# pulser_5.net
KiCad netlist of a schematic drawn in EAGLE
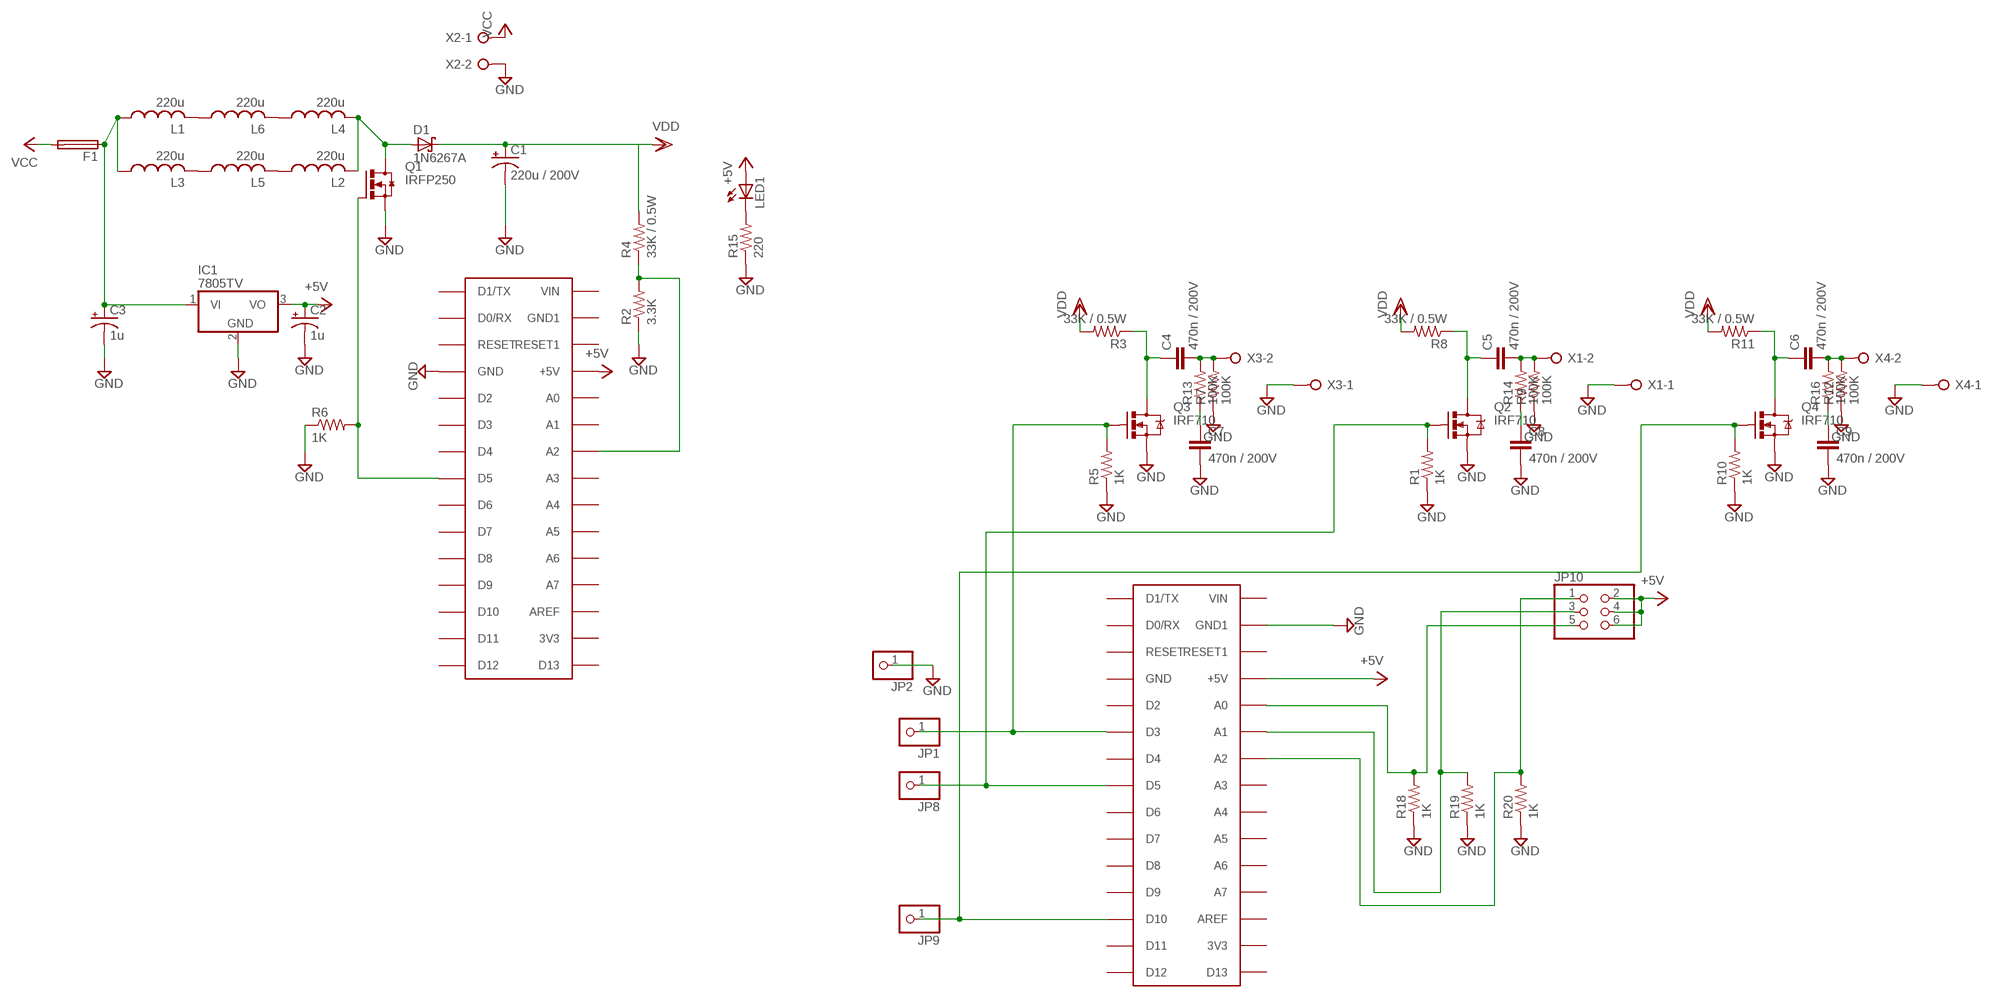
[diagram p0: schematic, sheet 1]

(export (version "E")
  (design (tool "Eeschema 10.0.6"))
  (components
    (comp (ref "C1")
      (value "220u / 200V")
      (footprint "eagle-import:E7,5-18")
      (libsource (lib "eagle-import") (part "CPOL-USE7.5-18"))
    )
    (comp (ref "C2")
      (value "1u")
      (footprint "eagle-import:E2,5-6")
      (libsource (lib "eagle-import") (part "CPOL-USE2.5-6"))
    )
    (comp (ref "C3")
      (value "1u")
      (footprint "eagle-import:E2,5-6")
      (libsource (lib "eagle-import") (part "CPOL-USE2.5-6"))
    )
    (comp (ref "C4")
      (value "470n / 200V")
      (footprint "eagle-import:C150-064X183")
      (libsource (lib "eagle-import") (part "C-EU150-064X183"))
    )
    (comp (ref "C5")
      (value "470n / 200V")
      (footprint "eagle-import:C150-064X183")
      (libsource (lib "eagle-import") (part "C-EU150-064X183"))
    )
    (comp (ref "C6")
      (value "470n / 200V")
      (footprint "eagle-import:C150-064X183")
      (libsource (lib "eagle-import") (part "C-EU150-064X183"))
    )
    (comp (ref "C7")
      (value "470n / 200V")
      (footprint "eagle-import:C150-064X183")
      (libsource (lib "eagle-import") (part "C-EU150-064X183"))
    )
    (comp (ref "C8")
      (value "470n / 200V")
      (footprint "eagle-import:C150-064X183")
      (libsource (lib "eagle-import") (part "C-EU150-064X183"))
    )
    (comp (ref "C9")
      (value "470n / 200V")
      (footprint "eagle-import:C150-064X183")
      (libsource (lib "eagle-import") (part "C-EU150-064X183"))
    )
    (comp (ref "D1")
      (value "1N6267A")
      (footprint "eagle-import:C4111-15")
      (libsource (lib "eagle-import") (part "1N6267A"))
    )
    (comp (ref "F1")
      (value "TE5")
      (footprint "eagle-import:TE5")
      (libsource (lib "eagle-import") (part "TE5"))
    )
    (comp (ref "IC1")
      (value "7805TV")
      (footprint "eagle-import:TO220V")
      (libsource (lib "eagle-import") (part "78TV05"))
    )
    (comp (ref "JP1")
      (value "PINHD-1X1")
      (footprint "eagle-import:1X01")
      (libsource (lib "eagle-import") (part "PINHD-1X1"))
    )
    (comp (ref "JP2")
      (value "PINHD-1X1")
      (footprint "eagle-import:1X01")
      (libsource (lib "eagle-import") (part "PINHD-1X1"))
    )
    (comp (ref "JP8")
      (value "PINHD-1X1")
      (footprint "eagle-import:1X01")
      (libsource (lib "eagle-import") (part "PINHD-1X1"))
    )
    (comp (ref "JP9")
      (value "PINHD-1X1")
      (footprint "eagle-import:1X01")
      (libsource (lib "eagle-import") (part "PINHD-1X1"))
    )
    (comp (ref "JP10")
      (value "PINHD-2X3")
      (footprint "eagle-import:2X03")
      (libsource (lib "eagle-import") (part "PINHD-2X3"))
    )
    (comp (ref "L1")
      (value "220u")
      (footprint "eagle-import:LAP02KR")
      (libsource (lib "eagle-import") (part "L-USLAP02KR"))
    )
    (comp (ref "L2")
      (value "220u")
      (footprint "eagle-import:LAP02KR")
      (libsource (lib "eagle-import") (part "L-USLAP02KR"))
    )
    (comp (ref "L3")
      (value "220u")
      (footprint "eagle-import:LAP02KR")
      (libsource (lib "eagle-import") (part "L-USLAP02KR"))
    )
    (comp (ref "L4")
      (value "220u")
      (footprint "eagle-import:LAP02KR")
      (libsource (lib "eagle-import") (part "L-USLAP02KR"))
    )
    (comp (ref "L5")
      (value "220u")
      (footprint "eagle-import:LAP02KR")
      (libsource (lib "eagle-import") (part "L-USLAP02KR"))
    )
    (comp (ref "L6")
      (value "220u")
      (footprint "eagle-import:LAP02KR")
      (libsource (lib "eagle-import") (part "L-USLAP02KR"))
    )
    (comp (ref "LED1")
      (value "LED5MM")
      (footprint "eagle-import:LED5MM")
      (libsource (lib "eagle-import") (part "LED5MM"))
    )
    (comp (ref "Q1")
      (value "IRFP250")
      (footprint "eagle-import:TO-247AD-V")
      (libsource (lib "eagle-import") (part "IRFP250"))
    )
    (comp (ref "Q2")
      (value "IRF710")
      (footprint "eagle-import:TO220V")
      (libsource (lib "eagle-import") (part "MOSFET-NCHANNELFQP30N06L"))
    )
    (comp (ref "Q3")
      (value "IRF710")
      (footprint "eagle-import:TO220V")
      (libsource (lib "eagle-import") (part "MOSFET-NCHANNELFQP30N06L"))
    )
    (comp (ref "Q4")
      (value "IRF710")
      (footprint "eagle-import:TO220V")
      (libsource (lib "eagle-import") (part "MOSFET-NCHANNELFQP30N06L"))
    )
    (comp (ref "R1")
      (value "1K")
      (footprint "eagle-import:0207_10")
      (libsource (lib "eagle-import") (part "R-US_0207/10"))
    )
    (comp (ref "R2")
      (value "3.3K")
      (footprint "eagle-import:0207_10")
      (libsource (lib "eagle-import") (part "R-US_0207/10"))
    )
    (comp (ref "R3")
      (value "33K / 0.5W")
      (footprint "eagle-import:0309_12")
      (libsource (lib "eagle-import") (part "R-US_0309/12"))
    )
    (comp (ref "R4")
      (value "33K / 0.5W")
      (footprint "eagle-import:0309_12")
      (libsource (lib "eagle-import") (part "R-US_0309/12"))
    )
    (comp (ref "R5")
      (value "1K")
      (footprint "eagle-import:0207_10")
      (libsource (lib "eagle-import") (part "R-US_0207/10"))
    )
    (comp (ref "R6")
      (value "1K")
      (footprint "eagle-import:0207_10")
      (libsource (lib "eagle-import") (part "R-US_0207/10"))
    )
    (comp (ref "R7")
      (value "100K")
      (footprint "eagle-import:0207_10")
      (libsource (lib "eagle-import") (part "R-US_0207/10"))
    )
    (comp (ref "R8")
      (value "33K / 0.5W")
      (footprint "eagle-import:0309_12")
      (libsource (lib "eagle-import") (part "R-US_0309/12"))
    )
    (comp (ref "R9")
      (value "100K")
      (footprint "eagle-import:0207_10")
      (libsource (lib "eagle-import") (part "R-US_0207/10"))
    )
    (comp (ref "R10")
      (value "1K")
      (footprint "eagle-import:0207_10")
      (libsource (lib "eagle-import") (part "R-US_0207/10"))
    )
    (comp (ref "R11")
      (value "33K / 0.5W")
      (footprint "eagle-import:0309_12")
      (libsource (lib "eagle-import") (part "R-US_0309/12"))
    )
    (comp (ref "R12")
      (value "100K")
      (footprint "eagle-import:0207_10")
      (libsource (lib "eagle-import") (part "R-US_0207/10"))
    )
    (comp (ref "R13")
      (value "100K")
      (footprint "eagle-import:0207_10")
      (libsource (lib "eagle-import") (part "R-US_0207/10"))
    )
    (comp (ref "R14")
      (value "100K")
      (footprint "eagle-import:0207_10")
      (libsource (lib "eagle-import") (part "R-US_0207/10"))
    )
    (comp (ref "R15")
      (value "220")
      (footprint "eagle-import:0207_10")
      (libsource (lib "eagle-import") (part "R-US_0207/10"))
    )
    (comp (ref "R16")
      (value "100K")
      (footprint "eagle-import:0207_10")
      (libsource (lib "eagle-import") (part "R-US_0207/10"))
    )
    (comp (ref "R18")
      (value "1K")
      (footprint "eagle-import:0207_10")
      (libsource (lib "eagle-import") (part "R-US_0207/10"))
    )
    (comp (ref "R19")
      (value "1K")
      (footprint "eagle-import:0207_10")
      (libsource (lib "eagle-import") (part "R-US_0207/10"))
    )
    (comp (ref "R20")
      (value "1K")
      (footprint "eagle-import:0207_10")
      (libsource (lib "eagle-import") (part "R-US_0207/10"))
    )
    (comp (ref "U$1")
      (value "ARDUINONANO")
      (footprint "eagle-import:PDIP-32")
      (libsource (lib "eagle-import") (part "ARDUINONANO"))
    )
    (comp (ref "U$2")
      (value "ARDUINONANO")
      (footprint "eagle-import:PDIP-32")
      (libsource (lib "eagle-import") (part "ARDUINONANO"))
    )
    (comp (ref "X1")
      (value "W237-02P")
      (footprint "eagle-import:W237-132")
      (libsource (lib "eagle-import") (part "W237-02P"))
    )
    (comp (ref "X2")
      (value "W237-02P")
      (footprint "eagle-import:W237-132")
      (libsource (lib "eagle-import") (part "W237-02P"))
    )
    (comp (ref "X3")
      (value "W237-02P")
      (footprint "eagle-import:W237-132")
      (libsource (lib "eagle-import") (part "W237-02P"))
    )
    (comp (ref "X4")
      (value "W237-02P")
      (footprint "eagle-import:W237-132")
      (libsource (lib "eagle-import") (part "W237-02P"))
    )
  )
  (nets
    (net (code "1") (name "+5V") (class "Default")
      (node (ref "C2") (pin "+") (pinfunction "+_+") (pintype "passive"))
      (node (ref "IC1") (pin "3") (pinfunction "VO_3") (pintype "passive"))
      (node (ref "JP10") (pin "2") (pinfunction "2_2") (pintype "passive"))
      (node (ref "JP10") (pin "4") (pinfunction "4_4") (pintype "passive"))
      (node (ref "JP10") (pin "6") (pinfunction "6_6") (pintype "passive"))
      (node (ref "LED1") (pin "A") (pinfunction "A_A") (pintype "passive"))
      (node (ref "U$1") (pin "+5V") (pinfunction "+5V_+5V") (pintype "bidirectional"))
      (node (ref "U$2") (pin "+5V") (pinfunction "+5V_+5V") (pintype "bidirectional"))
    )
    (net (code "2") (name "GND") (class "Default")
      (node (ref "C1") (pin "-") (pinfunction "-_-") (pintype "passive"))
      (node (ref "C2") (pin "-") (pinfunction "-_-") (pintype "passive"))
      (node (ref "C3") (pin "-") (pinfunction "-_-") (pintype "passive"))
      (node (ref "C7") (pin "2") (pinfunction "2_2") (pintype "passive"))
      (node (ref "C8") (pin "2") (pinfunction "2_2") (pintype "passive"))
      (node (ref "C9") (pin "2") (pinfunction "2_2") (pintype "passive"))
      (node (ref "IC1") (pin "2") (pinfunction "GND_2") (pintype "passive"))
      (node (ref "JP2") (pin "1") (pinfunction "1_1") (pintype "passive"))
      (node (ref "Q1") (pin "S") (pinfunction "S_S") (pintype "passive"))
      (node (ref "Q2") (pin "3") (pinfunction "S_3") (pintype "passive"))
      (node (ref "Q3") (pin "3") (pinfunction "S_3") (pintype "passive"))
      (node (ref "Q4") (pin "3") (pinfunction "S_3") (pintype "passive"))
      (node (ref "R1") (pin "1") (pinfunction "1_1") (pintype "passive"))
      (node (ref "R10") (pin "1") (pinfunction "1_1") (pintype "passive"))
      (node (ref "R12") (pin "1") (pinfunction "1_1") (pintype "passive"))
      (node (ref "R15") (pin "1") (pinfunction "1_1") (pintype "passive"))
      (node (ref "R18") (pin "1") (pinfunction "1_1") (pintype "passive"))
      (node (ref "R19") (pin "1") (pinfunction "1_1") (pintype "passive"))
      (node (ref "R2") (pin "1") (pinfunction "1_1") (pintype "passive"))
      (node (ref "R20") (pin "1") (pinfunction "1_1") (pintype "passive"))
      (node (ref "R5") (pin "1") (pinfunction "1_1") (pintype "passive"))
      (node (ref "R6") (pin "1") (pinfunction "1_1") (pintype "passive"))
      (node (ref "R7") (pin "1") (pinfunction "1_1") (pintype "passive"))
      (node (ref "R9") (pin "1") (pinfunction "1_1") (pintype "passive"))
      (node (ref "U$1") (pin "GND") (pinfunction "GND_GND") (pintype "bidirectional"))
      (node (ref "U$2") (pin "GND1") (pinfunction "GND1_GND1") (pintype "bidirectional"))
      (node (ref "X1") (pin "1") (pinfunction "KL_1") (pintype "passive"))
      (node (ref "X2") (pin "2") (pinfunction "KL_2") (pintype "passive"))
      (node (ref "X3") (pin "1") (pinfunction "KL_1") (pintype "passive"))
      (node (ref "X4") (pin "1") (pinfunction "KL_1") (pintype "passive"))
    )
    (net (code "3") (name "Net-(C7-Pad1)") (class "Default")
      (node (ref "C7") (pin "1") (pinfunction "1_1") (pintype "passive"))
      (node (ref "R13") (pin "1") (pinfunction "1_1") (pintype "passive"))
    )
    (net (code "4") (name "Net-(C8-Pad1)") (class "Default")
      (node (ref "C8") (pin "1") (pinfunction "1_1") (pintype "passive"))
      (node (ref "R14") (pin "1") (pinfunction "1_1") (pintype "passive"))
    )
    (net (code "5") (name "Net-(C9-Pad1)") (class "Default")
      (node (ref "C9") (pin "1") (pinfunction "1_1") (pintype "passive"))
      (node (ref "R16") (pin "1") (pinfunction "1_1") (pintype "passive"))
    )
    (net (code "6") (name "Net-(D1-PadA)") (class "Default")
      (node (ref "D1") (pin "A") (pinfunction "A_A") (pintype "passive"))
      (node (ref "L2") (pin "2") (pinfunction "2_2") (pintype "passive"))
      (node (ref "L4") (pin "2") (pinfunction "2_2") (pintype "passive"))
      (node (ref "Q1") (pin "D") (pinfunction "D_D") (pintype "passive"))
    )
    (net (code "7") (name "Net-(IC1-VI)") (class "Default")
      (node (ref "C3") (pin "+") (pinfunction "+_+") (pintype "passive"))
      (node (ref "F1") (pin "1") (pinfunction "1_1") (pintype "passive"))
      (node (ref "IC1") (pin "1") (pinfunction "VI_1") (pintype "input"))
      (node (ref "L1") (pin "1") (pinfunction "1_1") (pintype "passive"))
      (node (ref "L3") (pin "1") (pinfunction "1_1") (pintype "passive"))
    )
    (net (code "8") (name "Net-(JP10-Pad1)") (class "Default")
      (node (ref "JP10") (pin "1") (pinfunction "1_1") (pintype "passive"))
      (node (ref "R20") (pin "2") (pinfunction "2_2") (pintype "passive"))
      (node (ref "U$2") (pin "A2") (pinfunction "A2_A2") (pintype "bidirectional"))
    )
    (net (code "9") (name "Net-(JP10-Pad3)") (class "Default")
      (node (ref "JP10") (pin "3") (pinfunction "3_3") (pintype "passive"))
      (node (ref "R19") (pin "2") (pinfunction "2_2") (pintype "passive"))
      (node (ref "U$2") (pin "A1") (pinfunction "A1_A1") (pintype "bidirectional"))
    )
    (net (code "10") (name "Net-(JP10-Pad5)") (class "Default")
      (node (ref "JP10") (pin "5") (pinfunction "5_5") (pintype "passive"))
      (node (ref "R18") (pin "2") (pinfunction "2_2") (pintype "passive"))
      (node (ref "U$2") (pin "A0") (pinfunction "A0_A0") (pintype "bidirectional"))
    )
    (net (code "11") (name "Net-(L1-Pad2)") (class "Default")
      (node (ref "L1") (pin "2") (pinfunction "2_2") (pintype "passive"))
      (node (ref "L6") (pin "1") (pinfunction "1_1") (pintype "passive"))
    )
    (net (code "12") (name "Net-(L2-Pad1)") (class "Default")
      (node (ref "L2") (pin "1") (pinfunction "1_1") (pintype "passive"))
      (node (ref "L5") (pin "2") (pinfunction "2_2") (pintype "passive"))
    )
    (net (code "13") (name "Net-(L3-Pad2)") (class "Default")
      (node (ref "L3") (pin "2") (pinfunction "2_2") (pintype "passive"))
      (node (ref "L5") (pin "1") (pinfunction "1_1") (pintype "passive"))
    )
    (net (code "14") (name "Net-(L4-Pad1)") (class "Default")
      (node (ref "L4") (pin "1") (pinfunction "1_1") (pintype "passive"))
      (node (ref "L6") (pin "2") (pinfunction "2_2") (pintype "passive"))
    )
    (net (code "15") (name "Net-(LED1-C)") (class "Default")
      (node (ref "LED1") (pin "K") (pinfunction "C_K") (pintype "passive"))
      (node (ref "R15") (pin "2") (pinfunction "2_2") (pintype "passive"))
    )
    (net (code "16") (name "Net-(Q1-PadG)") (class "Default")
      (node (ref "Q1") (pin "G") (pinfunction "G_G") (pintype "passive"))
      (node (ref "R6") (pin "2") (pinfunction "2_2") (pintype "passive"))
      (node (ref "U$1") (pin "D5") (pinfunction "D5_D5") (pintype "bidirectional"))
    )
    (net (code "17") (name "Net-(Q2-D)") (class "Default")
      (node (ref "C5") (pin "1") (pinfunction "1_1") (pintype "passive"))
      (node (ref "Q2") (pin "2") (pinfunction "D_2") (pintype "passive"))
      (node (ref "R8") (pin "1") (pinfunction "1_1") (pintype "passive"))
    )
    (net (code "18") (name "Net-(Q2-G)") (class "Default")
      (node (ref "JP8") (pin "1") (pinfunction "1_1") (pintype "passive"))
      (node (ref "Q2") (pin "1") (pinfunction "G_1") (pintype "passive"))
      (node (ref "R1") (pin "2") (pinfunction "2_2") (pintype "passive"))
      (node (ref "U$2") (pin "D5") (pinfunction "D5_D5") (pintype "bidirectional"))
    )
    (net (code "19") (name "Net-(Q3-D)") (class "Default")
      (node (ref "C4") (pin "1") (pinfunction "1_1") (pintype "passive"))
      (node (ref "Q3") (pin "2") (pinfunction "D_2") (pintype "passive"))
      (node (ref "R3") (pin "1") (pinfunction "1_1") (pintype "passive"))
    )
    (net (code "20") (name "Net-(Q3-G)") (class "Default")
      (node (ref "JP1") (pin "1") (pinfunction "1_1") (pintype "passive"))
      (node (ref "Q3") (pin "1") (pinfunction "G_1") (pintype "passive"))
      (node (ref "R5") (pin "2") (pinfunction "2_2") (pintype "passive"))
      (node (ref "U$2") (pin "D3") (pinfunction "D3_D3") (pintype "bidirectional"))
    )
    (net (code "21") (name "Net-(Q4-D)") (class "Default")
      (node (ref "C6") (pin "1") (pinfunction "1_1") (pintype "passive"))
      (node (ref "Q4") (pin "2") (pinfunction "D_2") (pintype "passive"))
      (node (ref "R11") (pin "1") (pinfunction "1_1") (pintype "passive"))
    )
    (net (code "22") (name "Net-(Q4-G)") (class "Default")
      (node (ref "JP9") (pin "1") (pinfunction "1_1") (pintype "passive"))
      (node (ref "Q4") (pin "1") (pinfunction "G_1") (pintype "passive"))
      (node (ref "R10") (pin "2") (pinfunction "2_2") (pintype "passive"))
      (node (ref "U$2") (pin "D10") (pinfunction "D10_D10") (pintype "bidirectional"))
    )
    (net (code "23") (name "Net-(R2-Pad2)") (class "Default")
      (node (ref "R2") (pin "2") (pinfunction "2_2") (pintype "passive"))
      (node (ref "R4") (pin "1") (pinfunction "1_1") (pintype "passive"))
      (node (ref "U$1") (pin "A2") (pinfunction "A2_A2") (pintype "bidirectional"))
    )
    (net (code "24") (name "Net-(X1B-KL)") (class "Default")
      (node (ref "C5") (pin "2") (pinfunction "2_2") (pintype "passive"))
      (node (ref "R14") (pin "2") (pinfunction "2_2") (pintype "passive"))
      (node (ref "R9") (pin "2") (pinfunction "2_2") (pintype "passive"))
      (node (ref "X1") (pin "2") (pinfunction "KL_2") (pintype "passive"))
    )
    (net (code "25") (name "Net-(X3B-KL)") (class "Default")
      (node (ref "C4") (pin "2") (pinfunction "2_2") (pintype "passive"))
      (node (ref "R13") (pin "2") (pinfunction "2_2") (pintype "passive"))
      (node (ref "R7") (pin "2") (pinfunction "2_2") (pintype "passive"))
      (node (ref "X3") (pin "2") (pinfunction "KL_2") (pintype "passive"))
    )
    (net (code "26") (name "Net-(X4B-KL)") (class "Default")
      (node (ref "C6") (pin "2") (pinfunction "2_2") (pintype "passive"))
      (node (ref "R12") (pin "2") (pinfunction "2_2") (pintype "passive"))
      (node (ref "R16") (pin "2") (pinfunction "2_2") (pintype "passive"))
      (node (ref "X4") (pin "2") (pinfunction "KL_2") (pintype "passive"))
    )
    (net (code "27") (name "VCC") (class "Default")
      (node (ref "F1") (pin "2") (pinfunction "2_2") (pintype "passive"))
      (node (ref "X2") (pin "1") (pinfunction "KL_1") (pintype "passive"))
    )
    (net (code "28") (name "VDD") (class "Default")
      (node (ref "C1") (pin "+") (pinfunction "+_+") (pintype "passive"))
      (node (ref "D1") (pin "C") (pinfunction "C_C") (pintype "passive"))
      (node (ref "R11") (pin "2") (pinfunction "2_2") (pintype "passive"))
      (node (ref "R3") (pin "2") (pinfunction "2_2") (pintype "passive"))
      (node (ref "R4") (pin "2") (pinfunction "2_2") (pintype "passive"))
      (node (ref "R8") (pin "2") (pinfunction "2_2") (pintype "passive"))
    )
    (net (code "29") (name "unconnected-(U$1-Pad3V3)") (class "Default")
      (node (ref "U$1") (pin "3V3") (pinfunction "3V3_3V3") (pintype "bidirectional"))
    )
    (net (code "30") (name "unconnected-(U$1-PadA0)") (class "Default")
      (node (ref "U$1") (pin "A0") (pinfunction "A0_A0") (pintype "bidirectional"))
    )
    (net (code "31") (name "unconnected-(U$1-PadA1)") (class "Default")
      (node (ref "U$1") (pin "A1") (pinfunction "A1_A1") (pintype "bidirectional"))
    )
    (net (code "32") (name "unconnected-(U$1-PadA3)") (class "Default")
      (node (ref "U$1") (pin "A3") (pinfunction "A3_A3") (pintype "bidirectional"))
    )
    (net (code "33") (name "unconnected-(U$1-PadA4)") (class "Default")
      (node (ref "U$1") (pin "A4") (pinfunction "A4_A4") (pintype "bidirectional"))
    )
    (net (code "34") (name "unconnected-(U$1-PadA5)") (class "Default")
      (node (ref "U$1") (pin "A5") (pinfunction "A5_A5") (pintype "bidirectional"))
    )
    (net (code "35") (name "unconnected-(U$1-PadA6)") (class "Default")
      (node (ref "U$1") (pin "A6") (pinfunction "A6_A6") (pintype "bidirectional"))
    )
    (net (code "36") (name "unconnected-(U$1-PadA7)") (class "Default")
      (node (ref "U$1") (pin "A7") (pinfunction "A7_A7") (pintype "bidirectional"))
    )
    (net (code "37") (name "unconnected-(U$1-PadAREF)") (class "Default")
      (node (ref "U$1") (pin "AREF") (pinfunction "AREF_AREF") (pintype "bidirectional"))
    )
    (net (code "38") (name "unconnected-(U$1-PadD0{slash}RX)") (class "Default")
      (node (ref "U$1") (pin "D0/RX") (pinfunction "D0/RX_D0/RX") (pintype "bidirectional"))
    )
    (net (code "39") (name "unconnected-(U$1-PadD1{slash}TX)") (class "Default")
      (node (ref "U$1") (pin "D1/TX") (pinfunction "D1/TX_D1/TX") (pintype "bidirectional"))
    )
    (net (code "40") (name "unconnected-(U$1-PadD2)") (class "Default")
      (node (ref "U$1") (pin "D2") (pinfunction "D2_D2") (pintype "bidirectional"))
    )
    (net (code "41") (name "unconnected-(U$1-PadD3)") (class "Default")
      (node (ref "U$1") (pin "D3") (pinfunction "D3_D3") (pintype "bidirectional"))
    )
    (net (code "42") (name "unconnected-(U$1-PadD4)") (class "Default")
      (node (ref "U$1") (pin "D4") (pinfunction "D4_D4") (pintype "bidirectional"))
    )
    (net (code "43") (name "unconnected-(U$1-PadD6)") (class "Default")
      (node (ref "U$1") (pin "D6") (pinfunction "D6_D6") (pintype "bidirectional"))
    )
    (net (code "44") (name "unconnected-(U$1-PadD7)") (class "Default")
      (node (ref "U$1") (pin "D7") (pinfunction "D7_D7") (pintype "bidirectional"))
    )
    (net (code "45") (name "unconnected-(U$1-PadD8)") (class "Default")
      (node (ref "U$1") (pin "D8") (pinfunction "D8_D8") (pintype "bidirectional"))
    )
    (net (code "46") (name "unconnected-(U$1-PadD9)") (class "Default")
      (node (ref "U$1") (pin "D9") (pinfunction "D9_D9") (pintype "bidirectional"))
    )
    (net (code "47") (name "unconnected-(U$1-PadD10)") (class "Default")
      (node (ref "U$1") (pin "D10") (pinfunction "D10_D10") (pintype "bidirectional"))
    )
    (net (code "48") (name "unconnected-(U$1-PadD11)") (class "Default")
      (node (ref "U$1") (pin "D11") (pinfunction "D11_D11") (pintype "bidirectional"))
    )
    (net (code "49") (name "unconnected-(U$1-PadD12)") (class "Default")
      (node (ref "U$1") (pin "D12") (pinfunction "D12_D12") (pintype "bidirectional"))
    )
    (net (code "50") (name "unconnected-(U$1-PadD13)") (class "Default")
      (node (ref "U$1") (pin "D13") (pinfunction "D13_D13") (pintype "bidirectional"))
    )
    (net (code "51") (name "unconnected-(U$1-PadGND1)") (class "Default")
      (node (ref "U$1") (pin "GND1") (pinfunction "GND1_GND1") (pintype "bidirectional"))
    )
    (net (code "52") (name "unconnected-(U$1-PadRESET)") (class "Default")
      (node (ref "U$1") (pin "RESET") (pinfunction "RESET_RESET") (pintype "bidirectional"))
    )
    (net (code "53") (name "unconnected-(U$1-PadRESET1)") (class "Default")
      (node (ref "U$1") (pin "RESET1") (pinfunction "RESET1_RESET1") (pintype "bidirectional"))
    )
    (net (code "54") (name "unconnected-(U$1-PadVIN)") (class "Default")
      (node (ref "U$1") (pin "VIN") (pinfunction "VIN_VIN") (pintype "bidirectional"))
    )
    (net (code "55") (name "unconnected-(U$2-Pad3V3)") (class "Default")
      (node (ref "U$2") (pin "3V3") (pinfunction "3V3_3V3") (pintype "bidirectional"))
    )
    (net (code "56") (name "unconnected-(U$2-PadA3)") (class "Default")
      (node (ref "U$2") (pin "A3") (pinfunction "A3_A3") (pintype "bidirectional"))
    )
    (net (code "57") (name "unconnected-(U$2-PadA4)") (class "Default")
      (node (ref "U$2") (pin "A4") (pinfunction "A4_A4") (pintype "bidirectional"))
    )
    (net (code "58") (name "unconnected-(U$2-PadA5)") (class "Default")
      (node (ref "U$2") (pin "A5") (pinfunction "A5_A5") (pintype "bidirectional"))
    )
    (net (code "59") (name "unconnected-(U$2-PadA6)") (class "Default")
      (node (ref "U$2") (pin "A6") (pinfunction "A6_A6") (pintype "bidirectional"))
    )
    (net (code "60") (name "unconnected-(U$2-PadA7)") (class "Default")
      (node (ref "U$2") (pin "A7") (pinfunction "A7_A7") (pintype "bidirectional"))
    )
    (net (code "61") (name "unconnected-(U$2-PadAREF)") (class "Default")
      (node (ref "U$2") (pin "AREF") (pinfunction "AREF_AREF") (pintype "bidirectional"))
    )
    (net (code "62") (name "unconnected-(U$2-PadD0{slash}RX)") (class "Default")
      (node (ref "U$2") (pin "D0/RX") (pinfunction "D0/RX_D0/RX") (pintype "bidirectional"))
    )
    (net (code "63") (name "unconnected-(U$2-PadD1{slash}TX)") (class "Default")
      (node (ref "U$2") (pin "D1/TX") (pinfunction "D1/TX_D1/TX") (pintype "bidirectional"))
    )
    (net (code "64") (name "unconnected-(U$2-PadD2)") (class "Default")
      (node (ref "U$2") (pin "D2") (pinfunction "D2_D2") (pintype "bidirectional"))
    )
    (net (code "65") (name "unconnected-(U$2-PadD4)") (class "Default")
      (node (ref "U$2") (pin "D4") (pinfunction "D4_D4") (pintype "bidirectional"))
    )
    (net (code "66") (name "unconnected-(U$2-PadD6)") (class "Default")
      (node (ref "U$2") (pin "D6") (pinfunction "D6_D6") (pintype "bidirectional"))
    )
    (net (code "67") (name "unconnected-(U$2-PadD7)") (class "Default")
      (node (ref "U$2") (pin "D7") (pinfunction "D7_D7") (pintype "bidirectional"))
    )
    (net (code "68") (name "unconnected-(U$2-PadD8)") (class "Default")
      (node (ref "U$2") (pin "D8") (pinfunction "D8_D8") (pintype "bidirectional"))
    )
    (net (code "69") (name "unconnected-(U$2-PadD9)") (class "Default")
      (node (ref "U$2") (pin "D9") (pinfunction "D9_D9") (pintype "bidirectional"))
    )
    (net (code "70") (name "unconnected-(U$2-PadD11)") (class "Default")
      (node (ref "U$2") (pin "D11") (pinfunction "D11_D11") (pintype "bidirectional"))
    )
    (net (code "71") (name "unconnected-(U$2-PadD12)") (class "Default")
      (node (ref "U$2") (pin "D12") (pinfunction "D12_D12") (pintype "bidirectional"))
    )
    (net (code "72") (name "unconnected-(U$2-PadD13)") (class "Default")
      (node (ref "U$2") (pin "D13") (pinfunction "D13_D13") (pintype "bidirectional"))
    )
    (net (code "73") (name "unconnected-(U$2-PadGND)") (class "Default")
      (node (ref "U$2") (pin "GND") (pinfunction "GND_GND") (pintype "bidirectional"))
    )
    (net (code "74") (name "unconnected-(U$2-PadRESET)") (class "Default")
      (node (ref "U$2") (pin "RESET") (pinfunction "RESET_RESET") (pintype "bidirectional"))
    )
    (net (code "75") (name "unconnected-(U$2-PadRESET1)") (class "Default")
      (node (ref "U$2") (pin "RESET1") (pinfunction "RESET1_RESET1") (pintype "bidirectional"))
    )
    (net (code "76") (name "unconnected-(U$2-PadVIN)") (class "Default")
      (node (ref "U$2") (pin "VIN") (pinfunction "VIN_VIN") (pintype "bidirectional"))
    )
  )
)
